# BBB.net
KiCad netlist of a schematic drawn in Altium Designer
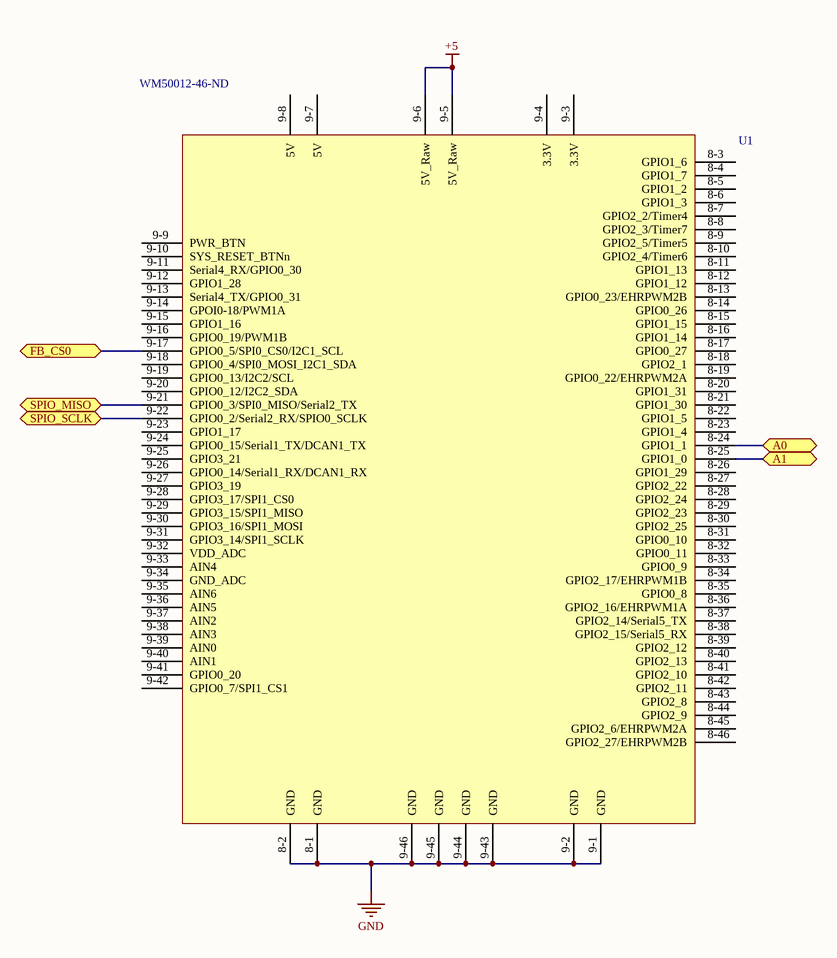
[diagram p0: BBB.SchDoc]

(export (version "E")
  (design (tool "Eeschema 10.0.6"))
  (components
    (comp (ref "U1")
      (value "BBB")
      (footprint "Beaglebone Black")
      (description "Beaglebone Black")
      (fields
        (field (name "SUPPLIER PART NUMBER 1") "WM50012-46-ND")
        (field (name "MANUFACTURER") "Molex, LLC")
        (field (name "MANUFACTURER PART NUMBER") "0010897462")
      )
      (libsource (lib "ZLS_Schematic_lib") (part "Beaglebone_Black"))
    )
  )
  (nets
    (net (code "1") (name "+5") (class "Default")
      (node (ref "U1") (pin "9-5") (pinfunction "5V_Raw_9-5") (pintype "passive"))
      (node (ref "U1") (pin "9-6") (pinfunction "5V_Raw_9-6") (pintype "passive"))
    )
    (net (code "2") (name "/A0") (class "Default")
      (node (ref "U1") (pin "8-24") (pinfunction "GPIO1_1_8-24") (pintype "passive"))
    )
    (net (code "3") (name "/A1") (class "Default")
      (node (ref "U1") (pin "8-25") (pinfunction "GPIO1_0_8-25") (pintype "passive"))
    )
    (net (code "4") (name "/FB_CS0") (class "Default")
      (node (ref "U1") (pin "9-17") (pinfunction "GPIO0_5/SPI0_CS0/I2C1_SCL_9-17") (pintype "passive"))
    )
    (net (code "5") (name "/SPIO_MISO") (class "Default")
      (node (ref "U1") (pin "9-21") (pinfunction "GPIO0_3/SPI0_MISO/Serial2_TX_9-21") (pintype "passive"))
    )
    (net (code "6") (name "/SPIO_SCLK") (class "Default")
      (node (ref "U1") (pin "9-22") (pinfunction "GPIO0_2/Serial2_RX/SPIO0_SCLK_9-22") (pintype "passive"))
    )
    (net (code "7") (name "GND") (class "Default")
      (node (ref "U1") (pin "8-1") (pinfunction "GND_8-1") (pintype "passive"))
      (node (ref "U1") (pin "8-2") (pinfunction "GND_8-2") (pintype "passive"))
      (node (ref "U1") (pin "9-1") (pinfunction "GND_9-1") (pintype "passive"))
      (node (ref "U1") (pin "9-2") (pinfunction "GND_9-2") (pintype "passive"))
      (node (ref "U1") (pin "9-43") (pinfunction "GND_9-43") (pintype "passive"))
      (node (ref "U1") (pin "9-44") (pinfunction "GND_9-44") (pintype "passive"))
      (node (ref "U1") (pin "9-45") (pinfunction "GND_9-45") (pintype "passive"))
      (node (ref "U1") (pin "9-46") (pinfunction "GND_9-46") (pintype "passive"))
    )
    (net (code "8") (name "unconnected-(U1-3.3V-Pad9-3)") (class "Default")
      (node (ref "U1") (pin "9-3") (pinfunction "3.3V_9-3") (pintype "passive"))
    )
    (net (code "9") (name "unconnected-(U1-3.3V-Pad9-4)") (class "Default")
      (node (ref "U1") (pin "9-4") (pinfunction "3.3V_9-4") (pintype "passive"))
    )
    (net (code "10") (name "unconnected-(U1-5V-Pad9-7)") (class "Default")
      (node (ref "U1") (pin "9-7") (pinfunction "5V_9-7") (pintype "passive"))
    )
    (net (code "11") (name "unconnected-(U1-5V-Pad9-8)") (class "Default")
      (node (ref "U1") (pin "9-8") (pinfunction "5V_9-8") (pintype "passive"))
    )
    (net (code "12") (name "unconnected-(U1-AIN0-Pad9-39)") (class "Default")
      (node (ref "U1") (pin "9-39") (pinfunction "AIN0_9-39") (pintype "passive"))
    )
    (net (code "13") (name "unconnected-(U1-AIN1-Pad9-40)") (class "Default")
      (node (ref "U1") (pin "9-40") (pinfunction "AIN1_9-40") (pintype "passive"))
    )
    (net (code "14") (name "unconnected-(U1-AIN2-Pad9-37)") (class "Default")
      (node (ref "U1") (pin "9-37") (pinfunction "AIN2_9-37") (pintype "passive"))
    )
    (net (code "15") (name "unconnected-(U1-AIN3-Pad9-38)") (class "Default")
      (node (ref "U1") (pin "9-38") (pinfunction "AIN3_9-38") (pintype "passive"))
    )
    (net (code "16") (name "unconnected-(U1-AIN4-Pad9-33)") (class "Default")
      (node (ref "U1") (pin "9-33") (pinfunction "AIN4_9-33") (pintype "passive"))
    )
    (net (code "17") (name "unconnected-(U1-AIN5-Pad9-36)") (class "Default")
      (node (ref "U1") (pin "9-36") (pinfunction "AIN5_9-36") (pintype "passive"))
    )
    (net (code "18") (name "unconnected-(U1-AIN6-Pad9-35)") (class "Default")
      (node (ref "U1") (pin "9-35") (pinfunction "AIN6_9-35") (pintype "passive"))
    )
    (net (code "19") (name "unconnected-(U1-GND_ADC-Pad9-34)") (class "Default")
      (node (ref "U1") (pin "9-34") (pinfunction "GND_ADC_9-34") (pintype "passive"))
    )
    (net (code "20") (name "unconnected-(U1-GPIO0_4{slash}SPI0_MOSI_I2C1_SDA-Pad9-18)") (class "Default")
      (node (ref "U1") (pin "9-18") (pinfunction "GPIO0_4/SPI0_MOSI_I2C1_SDA_9-18") (pintype "passive"))
    )
    (net (code "21") (name "unconnected-(U1-GPIO0_7{slash}SPI1_CS1-Pad9-42)") (class "Default")
      (node (ref "U1") (pin "9-42") (pinfunction "GPIO0_7/SPI1_CS1_9-42") (pintype "passive"))
    )
    (net (code "22") (name "unconnected-(U1-GPIO0_8-Pad8-35)") (class "Default")
      (node (ref "U1") (pin "8-35") (pinfunction "GPIO0_8_8-35") (pintype "passive"))
    )
    (net (code "23") (name "unconnected-(U1-GPIO0_9-Pad8-33)") (class "Default")
      (node (ref "U1") (pin "8-33") (pinfunction "GPIO0_9_8-33") (pintype "passive"))
    )
    (net (code "24") (name "unconnected-(U1-GPIO0_10-Pad8-31)") (class "Default")
      (node (ref "U1") (pin "8-31") (pinfunction "GPIO0_10_8-31") (pintype "passive"))
    )
    (net (code "25") (name "unconnected-(U1-GPIO0_11-Pad8-32)") (class "Default")
      (node (ref "U1") (pin "8-32") (pinfunction "GPIO0_11_8-32") (pintype "passive"))
    )
    (net (code "26") (name "unconnected-(U1-GPIO0_12{slash}I2C2_SDA-Pad9-20)") (class "Default")
      (node (ref "U1") (pin "9-20") (pinfunction "GPIO0_12/I2C2_SDA_9-20") (pintype "passive"))
    )
    (net (code "27") (name "unconnected-(U1-GPIO0_13{slash}I2C2{slash}SCL-Pad9-19)") (class "Default")
      (node (ref "U1") (pin "9-19") (pinfunction "GPIO0_13/I2C2/SCL_9-19") (pintype "passive"))
    )
    (net (code "28") (name "unconnected-(U1-GPIO0_14{slash}Serial1_RX{slash}DCAN1_RX-Pad9-26)") (class "Default")
      (node (ref "U1") (pin "9-26") (pinfunction "GPIO0_14/Serial1_RX/DCAN1_RX_9-26") (pintype "passive"))
    )
    (net (code "29") (name "unconnected-(U1-GPIO0_15{slash}Serial1_TX{slash}DCAN1_TX-Pad9-24)") (class "Default")
      (node (ref "U1") (pin "9-24") (pinfunction "GPIO0_15/Serial1_TX/DCAN1_TX_9-24") (pintype "passive"))
    )
    (net (code "30") (name "unconnected-(U1-GPIO0_19{slash}PWM1B-Pad9-16)") (class "Default")
      (node (ref "U1") (pin "9-16") (pinfunction "GPIO0_19/PWM1B_9-16") (pintype "passive"))
    )
    (net (code "31") (name "unconnected-(U1-GPIO0_20-Pad9-41)") (class "Default")
      (node (ref "U1") (pin "9-41") (pinfunction "GPIO0_20_9-41") (pintype "passive"))
    )
    (net (code "32") (name "unconnected-(U1-GPIO0_22{slash}EHRPWM2A-Pad8-19)") (class "Default")
      (node (ref "U1") (pin "8-19") (pinfunction "GPIO0_22/EHRPWM2A_8-19") (pintype "passive"))
    )
    (net (code "33") (name "unconnected-(U1-GPIO0_23{slash}EHRPWM2B-Pad8-13)") (class "Default")
      (node (ref "U1") (pin "8-13") (pinfunction "GPIO0_23/EHRPWM2B_8-13") (pintype "passive"))
    )
    (net (code "34") (name "unconnected-(U1-GPIO0_26-Pad8-14)") (class "Default")
      (node (ref "U1") (pin "8-14") (pinfunction "GPIO0_26_8-14") (pintype "passive"))
    )
    (net (code "35") (name "unconnected-(U1-GPIO0_27-Pad8-17)") (class "Default")
      (node (ref "U1") (pin "8-17") (pinfunction "GPIO0_27_8-17") (pintype "passive"))
    )
    (net (code "36") (name "unconnected-(U1-GPIO1_2-Pad8-5)") (class "Default")
      (node (ref "U1") (pin "8-5") (pinfunction "GPIO1_2_8-5") (pintype "passive"))
    )
    (net (code "37") (name "unconnected-(U1-GPIO1_3-Pad8-6)") (class "Default")
      (node (ref "U1") (pin "8-6") (pinfunction "GPIO1_3_8-6") (pintype "passive"))
    )
    (net (code "38") (name "unconnected-(U1-GPIO1_4-Pad8-23)") (class "Default")
      (node (ref "U1") (pin "8-23") (pinfunction "GPIO1_4_8-23") (pintype "passive"))
    )
    (net (code "39") (name "unconnected-(U1-GPIO1_5-Pad8-22)") (class "Default")
      (node (ref "U1") (pin "8-22") (pinfunction "GPIO1_5_8-22") (pintype "passive"))
    )
    (net (code "40") (name "unconnected-(U1-GPIO1_6-Pad8-3)") (class "Default")
      (node (ref "U1") (pin "8-3") (pinfunction "GPIO1_6_8-3") (pintype "passive"))
    )
    (net (code "41") (name "unconnected-(U1-GPIO1_7-Pad8-4)") (class "Default")
      (node (ref "U1") (pin "8-4") (pinfunction "GPIO1_7_8-4") (pintype "passive"))
    )
    (net (code "42") (name "unconnected-(U1-GPIO1_12-Pad8-12)") (class "Default")
      (node (ref "U1") (pin "8-12") (pinfunction "GPIO1_12_8-12") (pintype "passive"))
    )
    (net (code "43") (name "unconnected-(U1-GPIO1_13-Pad8-11)") (class "Default")
      (node (ref "U1") (pin "8-11") (pinfunction "GPIO1_13_8-11") (pintype "passive"))
    )
    (net (code "44") (name "unconnected-(U1-GPIO1_14-Pad8-16)") (class "Default")
      (node (ref "U1") (pin "8-16") (pinfunction "GPIO1_14_8-16") (pintype "passive"))
    )
    (net (code "45") (name "unconnected-(U1-GPIO1_15-Pad8-15)") (class "Default")
      (node (ref "U1") (pin "8-15") (pinfunction "GPIO1_15_8-15") (pintype "passive"))
    )
    (net (code "46") (name "unconnected-(U1-GPIO1_16-Pad9-15)") (class "Default")
      (node (ref "U1") (pin "9-15") (pinfunction "GPIO1_16_9-15") (pintype "passive"))
    )
    (net (code "47") (name "unconnected-(U1-GPIO1_17-Pad9-23)") (class "Default")
      (node (ref "U1") (pin "9-23") (pinfunction "GPIO1_17_9-23") (pintype "passive"))
    )
    (net (code "48") (name "unconnected-(U1-GPIO1_28-Pad9-12)") (class "Default")
      (node (ref "U1") (pin "9-12") (pinfunction "GPIO1_28_9-12") (pintype "passive"))
    )
    (net (code "49") (name "unconnected-(U1-GPIO1_29-Pad8-26)") (class "Default")
      (node (ref "U1") (pin "8-26") (pinfunction "GPIO1_29_8-26") (pintype "passive"))
    )
    (net (code "50") (name "unconnected-(U1-GPIO1_30-Pad8-21)") (class "Default")
      (node (ref "U1") (pin "8-21") (pinfunction "GPIO1_30_8-21") (pintype "passive"))
    )
    (net (code "51") (name "unconnected-(U1-GPIO1_31-Pad8-20)") (class "Default")
      (node (ref "U1") (pin "8-20") (pinfunction "GPIO1_31_8-20") (pintype "passive"))
    )
    (net (code "52") (name "unconnected-(U1-GPIO2_1-Pad8-18)") (class "Default")
      (node (ref "U1") (pin "8-18") (pinfunction "GPIO2_1_8-18") (pintype "passive"))
    )
    (net (code "53") (name "unconnected-(U1-GPIO2_2{slash}Timer4-Pad8-7)") (class "Default")
      (node (ref "U1") (pin "8-7") (pinfunction "GPIO2_2/Timer4_8-7") (pintype "passive"))
    )
    (net (code "54") (name "unconnected-(U1-GPIO2_3{slash}Timer7-Pad8-8)") (class "Default")
      (node (ref "U1") (pin "8-8") (pinfunction "GPIO2_3/Timer7_8-8") (pintype "passive"))
    )
    (net (code "55") (name "unconnected-(U1-GPIO2_4{slash}Timer6-Pad8-10)") (class "Default")
      (node (ref "U1") (pin "8-10") (pinfunction "GPIO2_4/Timer6_8-10") (pintype "passive"))
    )
    (net (code "56") (name "unconnected-(U1-GPIO2_5{slash}Timer5-Pad8-9)") (class "Default")
      (node (ref "U1") (pin "8-9") (pinfunction "GPIO2_5/Timer5_8-9") (pintype "passive"))
    )
    (net (code "57") (name "unconnected-(U1-GPIO2_6{slash}EHRPWM2A-Pad8-45)") (class "Default")
      (node (ref "U1") (pin "8-45") (pinfunction "GPIO2_6/EHRPWM2A_8-45") (pintype "passive"))
    )
    (net (code "58") (name "unconnected-(U1-GPIO2_8-Pad8-43)") (class "Default")
      (node (ref "U1") (pin "8-43") (pinfunction "GPIO2_8_8-43") (pintype "passive"))
    )
    (net (code "59") (name "unconnected-(U1-GPIO2_9-Pad8-44)") (class "Default")
      (node (ref "U1") (pin "8-44") (pinfunction "GPIO2_9_8-44") (pintype "passive"))
    )
    (net (code "60") (name "unconnected-(U1-GPIO2_10-Pad8-41)") (class "Default")
      (node (ref "U1") (pin "8-41") (pinfunction "GPIO2_10_8-41") (pintype "passive"))
    )
    (net (code "61") (name "unconnected-(U1-GPIO2_11-Pad8-42)") (class "Default")
      (node (ref "U1") (pin "8-42") (pinfunction "GPIO2_11_8-42") (pintype "passive"))
    )
    (net (code "62") (name "unconnected-(U1-GPIO2_12-Pad8-39)") (class "Default")
      (node (ref "U1") (pin "8-39") (pinfunction "GPIO2_12_8-39") (pintype "passive"))
    )
    (net (code "63") (name "unconnected-(U1-GPIO2_13-Pad8-40)") (class "Default")
      (node (ref "U1") (pin "8-40") (pinfunction "GPIO2_13_8-40") (pintype "passive"))
    )
    (net (code "64") (name "unconnected-(U1-GPIO2_14{slash}Serial5_TX-Pad8-37)") (class "Default")
      (node (ref "U1") (pin "8-37") (pinfunction "GPIO2_14/Serial5_TX_8-37") (pintype "passive"))
    )
    (net (code "65") (name "unconnected-(U1-GPIO2_15{slash}Serial5_RX-Pad8-38)") (class "Default")
      (node (ref "U1") (pin "8-38") (pinfunction "GPIO2_15/Serial5_RX_8-38") (pintype "passive"))
    )
    (net (code "66") (name "unconnected-(U1-GPIO2_16{slash}EHRPWM1A-Pad8-36)") (class "Default")
      (node (ref "U1") (pin "8-36") (pinfunction "GPIO2_16/EHRPWM1A_8-36") (pintype "passive"))
    )
    (net (code "67") (name "unconnected-(U1-GPIO2_17{slash}EHRPWM1B-Pad8-34)") (class "Default")
      (node (ref "U1") (pin "8-34") (pinfunction "GPIO2_17/EHRPWM1B_8-34") (pintype "passive"))
    )
    (net (code "68") (name "unconnected-(U1-GPIO2_22-Pad8-27)") (class "Default")
      (node (ref "U1") (pin "8-27") (pinfunction "GPIO2_22_8-27") (pintype "passive"))
    )
    (net (code "69") (name "unconnected-(U1-GPIO2_23-Pad8-29)") (class "Default")
      (node (ref "U1") (pin "8-29") (pinfunction "GPIO2_23_8-29") (pintype "passive"))
    )
    (net (code "70") (name "unconnected-(U1-GPIO2_24-Pad8-28)") (class "Default")
      (node (ref "U1") (pin "8-28") (pinfunction "GPIO2_24_8-28") (pintype "passive"))
    )
    (net (code "71") (name "unconnected-(U1-GPIO2_25-Pad8-30)") (class "Default")
      (node (ref "U1") (pin "8-30") (pinfunction "GPIO2_25_8-30") (pintype "passive"))
    )
    (net (code "72") (name "unconnected-(U1-GPIO2_27{slash}EHRPWM2B-Pad8-46)") (class "Default")
      (node (ref "U1") (pin "8-46") (pinfunction "GPIO2_27/EHRPWM2B_8-46") (pintype "passive"))
    )
    (net (code "73") (name "unconnected-(U1-GPIO3_14{slash}SPI1_SCLK-Pad9-31)") (class "Default")
      (node (ref "U1") (pin "9-31") (pinfunction "GPIO3_14/SPI1_SCLK_9-31") (pintype "passive"))
    )
    (net (code "74") (name "unconnected-(U1-GPIO3_15{slash}SPI1_MISO-Pad9-29)") (class "Default")
      (node (ref "U1") (pin "9-29") (pinfunction "GPIO3_15/SPI1_MISO_9-29") (pintype "passive"))
    )
    (net (code "75") (name "unconnected-(U1-GPIO3_16{slash}SPI1_MOSI-Pad9-30)") (class "Default")
      (node (ref "U1") (pin "9-30") (pinfunction "GPIO3_16/SPI1_MOSI_9-30") (pintype "passive"))
    )
    (net (code "76") (name "unconnected-(U1-GPIO3_17{slash}SPI1_CS0-Pad9-28)") (class "Default")
      (node (ref "U1") (pin "9-28") (pinfunction "GPIO3_17/SPI1_CS0_9-28") (pintype "passive"))
    )
    (net (code "77") (name "unconnected-(U1-GPIO3_19-Pad9-27)") (class "Default")
      (node (ref "U1") (pin "9-27") (pinfunction "GPIO3_19_9-27") (pintype "passive"))
    )
    (net (code "78") (name "unconnected-(U1-GPIO3_21-Pad9-25)") (class "Default")
      (node (ref "U1") (pin "9-25") (pinfunction "GPIO3_21_9-25") (pintype "passive"))
    )
    (net (code "79") (name "unconnected-(U1-GPOI0-18{slash}PWM1A-Pad9-14)") (class "Default")
      (node (ref "U1") (pin "9-14") (pinfunction "GPOI0-18/PWM1A_9-14") (pintype "passive"))
    )
    (net (code "80") (name "unconnected-(U1-PWR_BTN-Pad9-9)") (class "Default")
      (node (ref "U1") (pin "9-9") (pinfunction "PWR_BTN_9-9") (pintype "passive"))
    )
    (net (code "81") (name "unconnected-(U1-SYS_RESET_BTNn-Pad9-10)") (class "Default")
      (node (ref "U1") (pin "9-10") (pinfunction "SYS_RESET_BTNn_9-10") (pintype "passive"))
    )
    (net (code "82") (name "unconnected-(U1-Serial4_RX{slash}GPIO0_30-Pad9-11)") (class "Default")
      (node (ref "U1") (pin "9-11") (pinfunction "Serial4_RX/GPIO0_30_9-11") (pintype "passive"))
    )
    (net (code "83") (name "unconnected-(U1-Serial4_TX{slash}GPIO0_31-Pad9-13)") (class "Default")
      (node (ref "U1") (pin "9-13") (pinfunction "Serial4_TX/GPIO0_31_9-13") (pintype "passive"))
    )
    (net (code "84") (name "unconnected-(U1-VDD_ADC-Pad9-32)") (class "Default")
      (node (ref "U1") (pin "9-32") (pinfunction "VDD_ADC_9-32") (pintype "passive"))
    )
  )
)
